# Base_borne_conn.net
KiCad netlist of a schematic drawn in Altium Designer
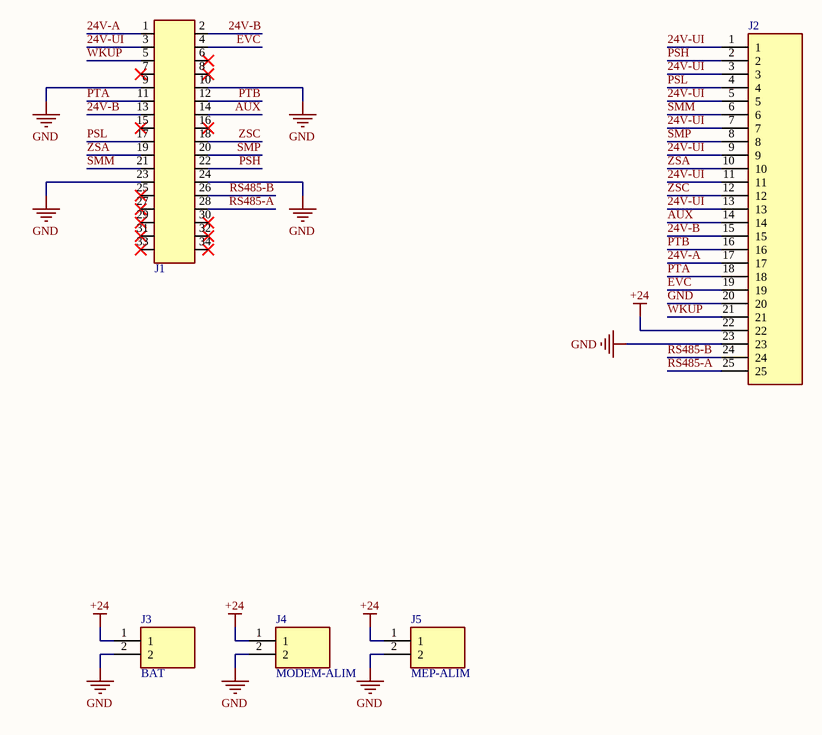
[diagram p0: Base_borne_conn.SchDoc]

(export (version "E")
  (design (tool "Eeschema 10.0.6"))
  (components
    (comp (ref "J1")
      (value "6120XX21621_61203421621")
      (footprint "61203421621")
      (description "34 pins, straight, gold plating")
      (fields (field (name "MF") "Wurth Electronics") (field (name "MP") "61203421621"))
      (libsource (lib "Base_borne_MEP_1") (part "6120XX21621_61203421621"))
    )
    (comp (ref "J2")
      (value "1769-25")
      (footprint "1769-25")
      (libsource (lib "Base_borne_MEP_1") (part "1769-25"))
    )
    (comp (ref "J3")
      (value "BAT")
      (footprint "1769463")
      (description "Connector")
      (fields (field (name "MANUFACTURER_PART_NUMBER") "1769463"))
      (libsource (lib "Base_borne_MEP_1") (part "1769463_1"))
    )
    (comp (ref "J4")
      (value "MODEM-ALIM")
      (footprint "1769463")
      (description "Connector")
      (fields (field (name "MANUFACTURER_PART_NUMBER") "1769463"))
      (libsource (lib "Base_borne_MEP_1") (part "1769463_2"))
    )
    (comp (ref "J5")
      (value "MEP-ALIM")
      (footprint "1769463")
      (description "Connector")
      (fields (field (name "MANUFACTURER_PART_NUMBER") "1769463"))
      (libsource (lib "Base_borne_MEP_1") (part "1769463"))
    )
  )
  (nets
    (net (code "1") (name "+24") (class "Default")
      (node (ref "J2") (pin "22") (pinfunction "22_22") (pintype "passive"))
      (node (ref "J3") (pin "1") (pinfunction "1_1") (pintype "passive"))
      (node (ref "J4") (pin "1") (pinfunction "1_1") (pintype "passive"))
      (node (ref "J5") (pin "1") (pinfunction "1_1") (pintype "passive"))
    )
    (net (code "2") (name "/24V-A") (class "Default")
      (node (ref "J1") (pin "1") (pinfunction "1_1") (pintype "passive"))
      (node (ref "J2") (pin "17") (pinfunction "17_17") (pintype "passive"))
    )
    (net (code "3") (name "/24V-B") (class "Default")
      (node (ref "J1") (pin "13") (pinfunction "13_13") (pintype "passive"))
      (node (ref "J1") (pin "2") (pinfunction "2_2") (pintype "passive"))
      (node (ref "J2") (pin "15") (pinfunction "15_15") (pintype "passive"))
    )
    (net (code "4") (name "/24V-UI") (class "Default")
      (node (ref "J1") (pin "3") (pinfunction "3_3") (pintype "passive"))
      (node (ref "J2") (pin "1") (pinfunction "1_1") (pintype "passive"))
      (node (ref "J2") (pin "11") (pinfunction "11_11") (pintype "passive"))
      (node (ref "J2") (pin "13") (pinfunction "13_13") (pintype "passive"))
      (node (ref "J2") (pin "3") (pinfunction "3_3") (pintype "passive"))
      (node (ref "J2") (pin "5") (pinfunction "5_5") (pintype "passive"))
      (node (ref "J2") (pin "7") (pinfunction "7_7") (pintype "passive"))
      (node (ref "J2") (pin "9") (pinfunction "9_9") (pintype "passive"))
    )
    (net (code "5") (name "/AUX") (class "Default")
      (node (ref "J1") (pin "14") (pinfunction "14_14") (pintype "passive"))
      (node (ref "J2") (pin "14") (pinfunction "14_14") (pintype "passive"))
    )
    (net (code "6") (name "/EVC") (class "Default")
      (node (ref "J1") (pin "4") (pinfunction "4_4") (pintype "passive"))
      (node (ref "J2") (pin "19") (pinfunction "19_19") (pintype "passive"))
    )
    (net (code "7") (name "/PSH") (class "Default")
      (node (ref "J1") (pin "22") (pinfunction "22_22") (pintype "passive"))
      (node (ref "J2") (pin "2") (pinfunction "2_2") (pintype "passive"))
    )
    (net (code "8") (name "/PSL") (class "Default")
      (node (ref "J1") (pin "17") (pinfunction "17_17") (pintype "passive"))
      (node (ref "J2") (pin "4") (pinfunction "4_4") (pintype "passive"))
    )
    (net (code "9") (name "/PTA") (class "Default")
      (node (ref "J1") (pin "11") (pinfunction "11_11") (pintype "passive"))
      (node (ref "J2") (pin "18") (pinfunction "18_18") (pintype "passive"))
    )
    (net (code "10") (name "/PTB") (class "Default")
      (node (ref "J1") (pin "12") (pinfunction "12_12") (pintype "passive"))
      (node (ref "J2") (pin "16") (pinfunction "16_16") (pintype "passive"))
    )
    (net (code "11") (name "/RS485-A") (class "Default")
      (node (ref "J1") (pin "28") (pinfunction "28_28") (pintype "passive"))
      (node (ref "J2") (pin "25") (pinfunction "25_25") (pintype "passive"))
    )
    (net (code "12") (name "/RS485-B") (class "Default")
      (node (ref "J1") (pin "26") (pinfunction "26_26") (pintype "passive"))
      (node (ref "J2") (pin "24") (pinfunction "24_24") (pintype "passive"))
    )
    (net (code "13") (name "/SMM") (class "Default")
      (node (ref "J1") (pin "21") (pinfunction "21_21") (pintype "passive"))
      (node (ref "J2") (pin "6") (pinfunction "6_6") (pintype "passive"))
    )
    (net (code "14") (name "/SMP") (class "Default")
      (node (ref "J1") (pin "20") (pinfunction "20_20") (pintype "passive"))
      (node (ref "J2") (pin "8") (pinfunction "8_8") (pintype "passive"))
    )
    (net (code "15") (name "/WKUP") (class "Default")
      (node (ref "J1") (pin "5") (pinfunction "5_5") (pintype "passive"))
      (node (ref "J2") (pin "21") (pinfunction "21_21") (pintype "passive"))
    )
    (net (code "16") (name "/ZSA") (class "Default")
      (node (ref "J1") (pin "19") (pinfunction "19_19") (pintype "passive"))
      (node (ref "J2") (pin "10") (pinfunction "10_10") (pintype "passive"))
    )
    (net (code "17") (name "/ZSC") (class "Default")
      (node (ref "J1") (pin "18") (pinfunction "18_18") (pintype "passive"))
      (node (ref "J2") (pin "12") (pinfunction "12_12") (pintype "passive"))
    )
    (net (code "18") (name "GND") (class "Default")
      (node (ref "J1") (pin "10") (pinfunction "10_10") (pintype "passive"))
      (node (ref "J1") (pin "23") (pinfunction "23_23") (pintype "passive"))
      (node (ref "J1") (pin "24") (pinfunction "24_24") (pintype "passive"))
      (node (ref "J1") (pin "9") (pinfunction "9_9") (pintype "passive"))
      (node (ref "J2") (pin "20") (pinfunction "20_20") (pintype "passive"))
      (node (ref "J2") (pin "23") (pinfunction "23_23") (pintype "passive"))
      (node (ref "J3") (pin "2") (pinfunction "2_2") (pintype "passive"))
      (node (ref "J4") (pin "2") (pinfunction "2_2") (pintype "passive"))
      (node (ref "J5") (pin "2") (pinfunction "2_2") (pintype "passive"))
    )
    (net (code "19") (name "unconnected-(J1-Pad6)") (class "Default")
      (node (ref "J1") (pin "6") (pinfunction "6_6") (pintype "passive+no_connect"))
    )
    (net (code "20") (name "unconnected-(J1-Pad7)") (class "Default")
      (node (ref "J1") (pin "7") (pinfunction "7_7") (pintype "passive+no_connect"))
    )
    (net (code "21") (name "unconnected-(J1-Pad8)") (class "Default")
      (node (ref "J1") (pin "8") (pinfunction "8_8") (pintype "passive+no_connect"))
    )
    (net (code "22") (name "unconnected-(J1-Pad15)") (class "Default")
      (node (ref "J1") (pin "15") (pinfunction "15_15") (pintype "passive+no_connect"))
    )
    (net (code "23") (name "unconnected-(J1-Pad16)") (class "Default")
      (node (ref "J1") (pin "16") (pinfunction "16_16") (pintype "passive+no_connect"))
    )
    (net (code "24") (name "unconnected-(J1-Pad25)") (class "Default")
      (node (ref "J1") (pin "25") (pinfunction "25_25") (pintype "passive+no_connect"))
    )
    (net (code "25") (name "unconnected-(J1-Pad27)") (class "Default")
      (node (ref "J1") (pin "27") (pinfunction "27_27") (pintype "passive+no_connect"))
    )
    (net (code "26") (name "unconnected-(J1-Pad29)") (class "Default")
      (node (ref "J1") (pin "29") (pinfunction "29_29") (pintype "passive+no_connect"))
    )
    (net (code "27") (name "unconnected-(J1-Pad30)") (class "Default")
      (node (ref "J1") (pin "30") (pinfunction "30_30") (pintype "passive+no_connect"))
    )
    (net (code "28") (name "unconnected-(J1-Pad31)") (class "Default")
      (node (ref "J1") (pin "31") (pinfunction "31_31") (pintype "passive+no_connect"))
    )
    (net (code "29") (name "unconnected-(J1-Pad32)") (class "Default")
      (node (ref "J1") (pin "32") (pinfunction "32_32") (pintype "passive+no_connect"))
    )
    (net (code "30") (name "unconnected-(J1-Pad33)") (class "Default")
      (node (ref "J1") (pin "33") (pinfunction "33_33") (pintype "passive+no_connect"))
    )
    (net (code "31") (name "unconnected-(J1-Pad34)") (class "Default")
      (node (ref "J1") (pin "34") (pinfunction "34_34") (pintype "passive+no_connect"))
    )
  )
)
